# fillcap_amp.net
KiCad netlist of a schematic drawn in Altium Designer
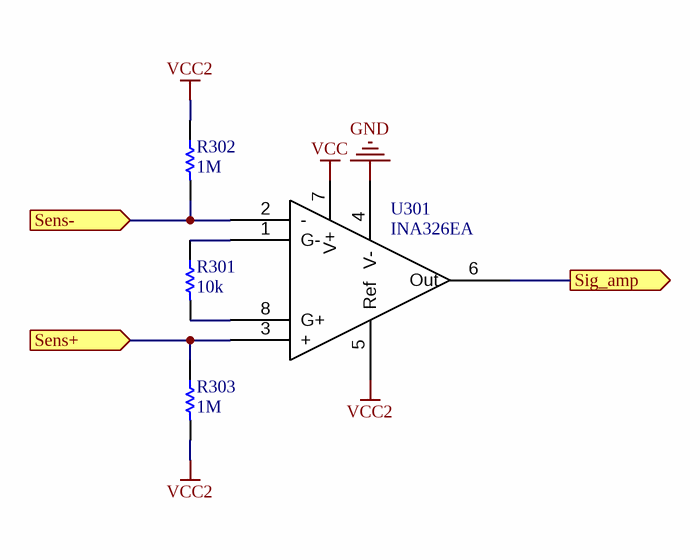
[diagram p0: fillcap_amp.SchDoc]

(export (version "E")
  (design (tool "Eeschema 10.0.6"))
  (components
    (comp (ref "R301")
      (value "10k")
      (footprint "ERA-0805")
      (fields (field (name "PUBLISHER") "Altium Limited"))
      (libsource (lib "Panasonic Resistor") (part "ERAS"))
    )
    (comp (ref "R302")
      (value "1M")
      (footprint "ERA-0805")
      (fields (field (name "PUBLISHER") "Altium Limited"))
      (libsource (lib "Panasonic Resistor") (part "ERAS"))
    )
    (comp (ref "R303")
      (value "1M")
      (footprint "ERA-0805")
      (fields (field (name "PUBLISHER") "Altium Limited"))
      (libsource (lib "Panasonic Resistor") (part "ERAS"))
    )
    (comp (ref "U301")
      (value "INA326EA")
      (footprint "VSSOP8(0.65mm)")
      (libsource (lib "fillcap_lib") (part "INA326EA"))
    )
  )
  (nets
    (net (code "1") (name "/Sens+") (class "Default")
      (node (ref "R303") (pin "1") (pinfunction "1_1") (pintype "passive"))
      (node (ref "U301") (pin "3") (pinfunction "+_3") (pintype "passive"))
    )
    (net (code "2") (name "/Sens-") (class "Default")
      (node (ref "R302") (pin "2") (pinfunction "2_2") (pintype "passive"))
      (node (ref "U301") (pin "2") (pinfunction "-_2") (pintype "passive"))
    )
    (net (code "3") (name "/Sig_amp") (class "Default")
      (node (ref "U301") (pin "6") (pinfunction "Out_6") (pintype "passive"))
    )
    (net (code "4") (name "GND") (class "Default")
      (node (ref "U301") (pin "4") (pinfunction "V-_4") (pintype "passive"))
    )
    (net (code "5") (name "Net-(U301-G+)") (class "Default")
      (node (ref "R301") (pin "2") (pinfunction "2_2") (pintype "passive"))
      (node (ref "U301") (pin "8") (pinfunction "G+_8") (pintype "passive"))
    )
    (net (code "6") (name "Net-(U301-G-)") (class "Default")
      (node (ref "R301") (pin "1") (pinfunction "1_1") (pintype "passive"))
      (node (ref "U301") (pin "1") (pinfunction "G-_1") (pintype "passive"))
    )
    (net (code "7") (name "VCC") (class "Default")
      (node (ref "U301") (pin "7") (pinfunction "V+_7") (pintype "passive"))
    )
    (net (code "8") (name "VCC2") (class "Default")
      (node (ref "R302") (pin "1") (pinfunction "1_1") (pintype "passive"))
      (node (ref "R303") (pin "2") (pinfunction "2_2") (pintype "passive"))
      (node (ref "U301") (pin "5") (pinfunction "Ref_5") (pintype "passive"))
    )
  )
)
